# Battery_Charger.net
KiCad netlist of a schematic drawn in Altium Designer
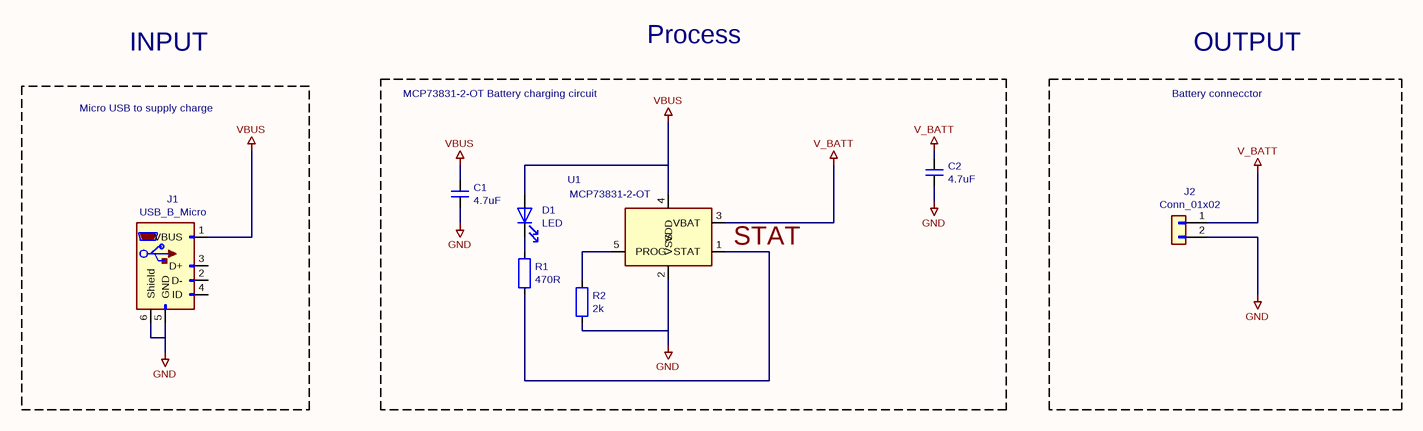
[diagram p0: Battery Charger.SchDoc]

(export (version "E")
  (design (tool "Eeschema 10.0.6"))
  (components
    (comp (ref "C1") (value "4.7uF") (libsource (lib "Device") (part "C_Small")))
    (comp (ref "C2") (value "4.7uF") (libsource (lib "Device") (part "C_Small")))
    (comp (ref "D1") (value "LED") (libsource (lib "Device") (part "LED")))
    (comp (ref "J1") (value "USB_B_Micro") (libsource (lib "Connector") (part "USB_B_Micro")))
    (comp (ref "J2") (value "Conn_01x02") (libsource (lib "Connector_Generic") (part "Conn_01x02")))
    (comp (ref "R1") (value "470R") (libsource (lib "Device") (part "R")))
    (comp (ref "R2") (value "2k") (libsource (lib "Device") (part "R")))
    (comp (ref "U1") (value "MCP73831-2-OT") (libsource (lib "Battery_Management") (part "MCP73831-2-OT")))
  )
  (nets
    (net (code "1") (name "/STAT") (class "Default")
      (node (ref "R1") (pin "2") (pinfunction "2_2") (pintype "passive"))
      (node (ref "U1") (pin "1") (pinfunction "STAT_1") (pintype "passive"))
    )
    (net (code "2") (name "GND") (class "Default")
      (node (ref "C1") (pin "2") (pinfunction "2_2") (pintype "passive"))
      (node (ref "C2") (pin "2") (pinfunction "2_2") (pintype "passive"))
      (node (ref "J1") (pin "5") (pinfunction "GND_5") (pintype "passive"))
      (node (ref "J1") (pin "6") (pinfunction "Shield_6") (pintype "passive"))
      (node (ref "J2") (pin "2") (pinfunction "Pin_2_2") (pintype "passive"))
      (node (ref "R2") (pin "2") (pinfunction "2_2") (pintype "passive"))
      (node (ref "U1") (pin "2") (pinfunction "VSS_2") (pintype "passive"))
    )
    (net (code "3") (name "Net-(D1-K)") (class "Default")
      (node (ref "D1") (pin "1") (pinfunction "K_1") (pintype "passive"))
      (node (ref "R1") (pin "1") (pinfunction "1_1") (pintype "passive"))
    )
    (net (code "4") (name "Net-(U1-PROG)") (class "Default")
      (node (ref "R2") (pin "1") (pinfunction "1_1") (pintype "passive"))
      (node (ref "U1") (pin "5") (pinfunction "PROG_5") (pintype "passive"))
    )
    (net (code "5") (name "VBUS") (class "Default")
      (node (ref "C1") (pin "1") (pinfunction "1_1") (pintype "passive"))
      (node (ref "D1") (pin "2") (pinfunction "A_2") (pintype "passive"))
      (node (ref "J1") (pin "1") (pinfunction "VBUS_1") (pintype "passive"))
      (node (ref "U1") (pin "4") (pinfunction "VDD_4") (pintype "passive"))
    )
    (net (code "6") (name "V_BATT") (class "Default")
      (node (ref "C2") (pin "1") (pinfunction "1_1") (pintype "passive"))
      (node (ref "J2") (pin "1") (pinfunction "Pin_1_1") (pintype "passive"))
      (node (ref "U1") (pin "3") (pinfunction "VBAT_3") (pintype "passive"))
    )
    (net (code "7") (name "unconnected-(J1-D+-Pad3)") (class "Default")
      (node (ref "J1") (pin "3") (pinfunction "D+_3") (pintype "passive"))
    )
    (net (code "8") (name "unconnected-(J1-D--Pad2)") (class "Default")
      (node (ref "J1") (pin "2") (pinfunction "D-_2") (pintype "passive"))
    )
    (net (code "9") (name "unconnected-(J1-ID-Pad4)") (class "Default")
      (node (ref "J1") (pin "4") (pinfunction "ID_4") (pintype "passive"))
    )
  )
)
